# SCH_sensoresAgua_2026-07-03.net
KiCad netlist of a schematic drawn in EasyEDA
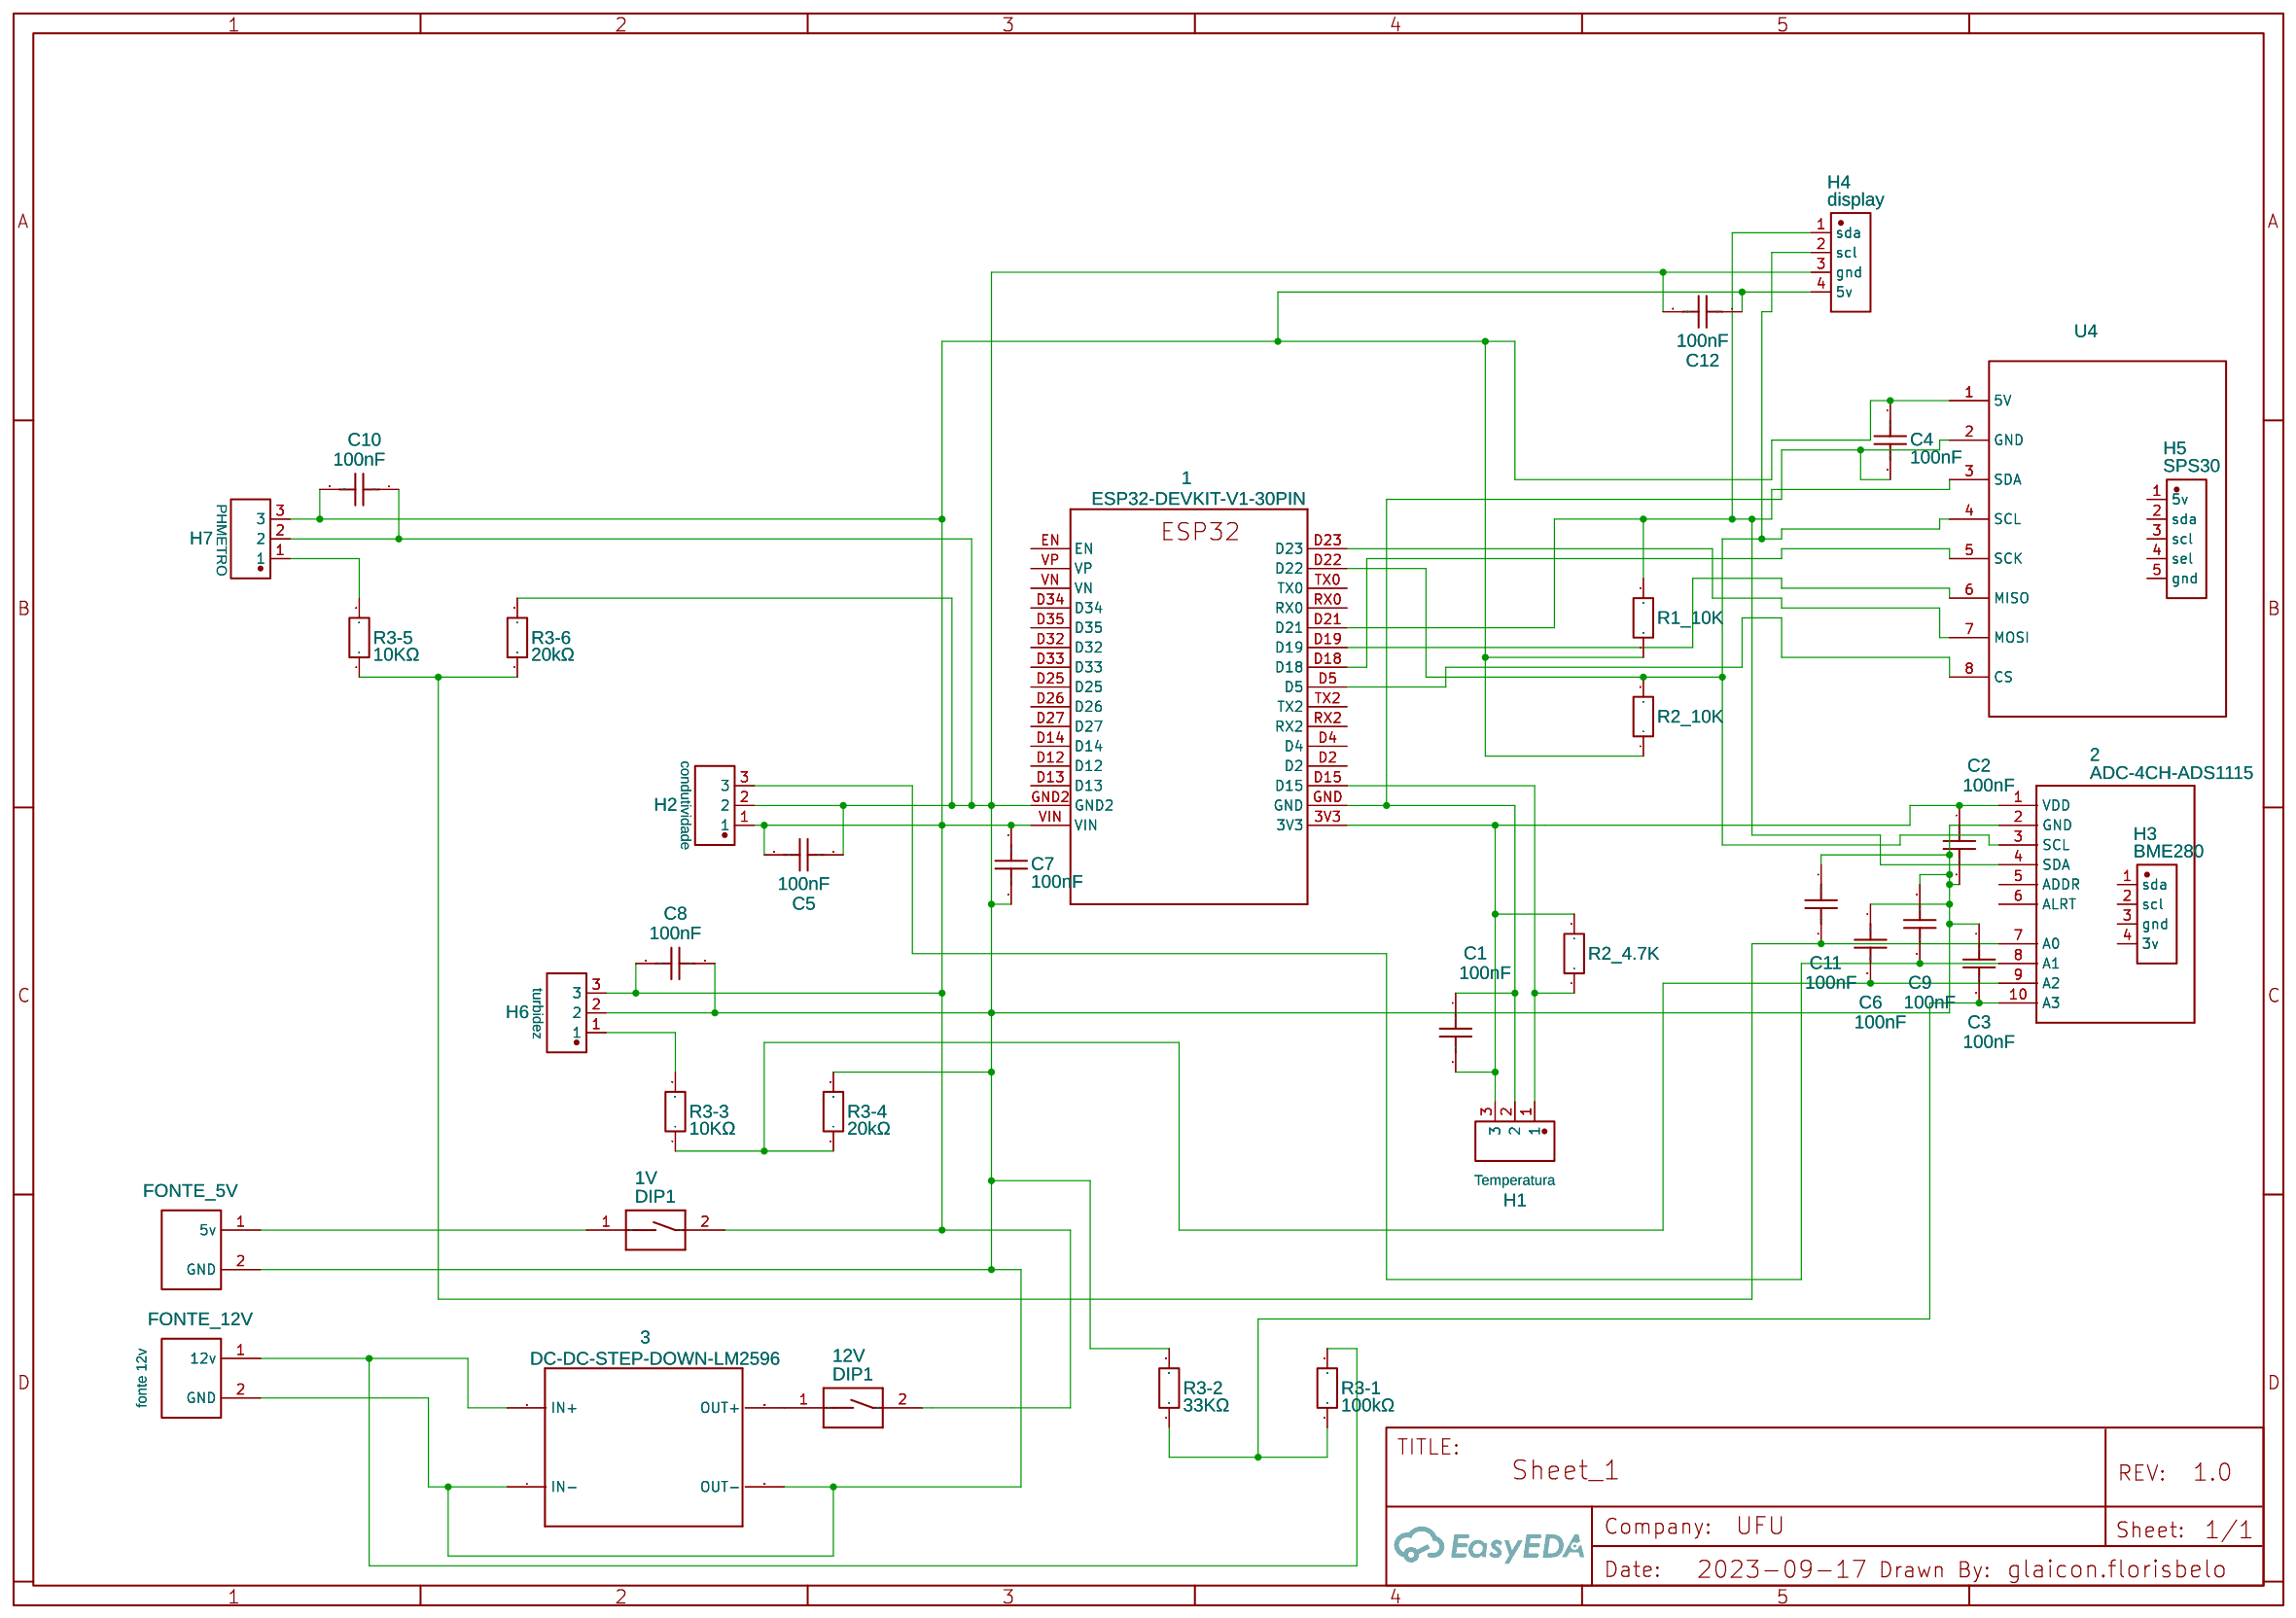
[diagram p0: schematic sheet]

(export (version "E")
  (design (tool "Eeschema 10.0.6"))
  (components
    (comp (ref "1") (value "ESP32-DEVKIT-V1-30PIN") (libsource (lib "") (part "ESP32-DEVKIT-V1-30PIN")))
    (comp (ref "1V")
      (value "DIP1")
      (fields
        (field (name "Manufacturer Part") "A6TN-1101")
        (field (name "Manufacturer") "Omron Electronics Inc-EMC Div")
      )
      (libsource (lib "") (part "DIP1"))
    )
    (comp (ref "2") (value "ADC-4CH-ADS1115") (libsource (lib "") (part "ADC-4CH-ADS1115")))
    (comp (ref "3") (value "DC-DC-STEP-DOWN-LM2596") (libsource (lib "") (part "DC-DC-STEP-DOWN-LM2596")))
    (comp (ref "12V")
      (value "DIP1")
      (fields
        (field (name "Manufacturer Part") "A6TN-1101")
        (field (name "Manufacturer") "Omron Electronics Inc-EMC Div")
      )
      (libsource (lib "") (part "DIP1_1"))
    )
    (comp (ref "C1")
      (value "100nF")
      (fields
        (field (name "Manufacturer Part") "CC1H104MC1FD3F6C10MF")
        (field (name "Manufacturer") "Dersonic(德尔创)")
      )
      (libsource (lib "") (part "CC1H104MC1FD3F6C10MF_1"))
    )
    (comp (ref "C2")
      (value "100nF")
      (fields
        (field (name "Manufacturer Part") "CC1H104MC1FD3F6C10MF")
        (field (name "Manufacturer") "Dersonic(德尔创)")
      )
      (libsource (lib "") (part "CC1H104MC1FD3F6C10MF_1"))
    )
    (comp (ref "C3")
      (value "100nF")
      (fields
        (field (name "Manufacturer Part") "CC1H104MC1FD3F6C10MF")
        (field (name "Manufacturer") "Dersonic(德尔创)")
      )
      (libsource (lib "") (part "CC1H104MC1FD3F6C10MF_1"))
    )
    (comp (ref "C4")
      (value "100nF")
      (fields
        (field (name "Manufacturer Part") "CC1H104MC1FD3F6C10MF")
        (field (name "Manufacturer") "Dersonic(德尔创)")
      )
      (libsource (lib "") (part "CC1H104MC1FD3F6C10MF_1"))
    )
    (comp (ref "C5")
      (value "100nF")
      (fields
        (field (name "Manufacturer Part") "CC1H104MC1FD3F6C10MF")
        (field (name "Manufacturer") "Dersonic(德尔创)")
      )
      (libsource (lib "") (part "CC1H104MC1FD3F6C10MF"))
    )
    (comp (ref "C6")
      (value "100nF")
      (fields
        (field (name "Manufacturer Part") "CC1H104MC1FD3F6C10MF")
        (field (name "Manufacturer") "Dersonic(德尔创)")
      )
      (libsource (lib "") (part "CC1H104MC1FD3F6C10MF_1"))
    )
    (comp (ref "C7")
      (value "100nF")
      (fields
        (field (name "Manufacturer Part") "CC1H104MC1FD3F6C10MF")
        (field (name "Manufacturer") "Dersonic(德尔创)")
      )
      (libsource (lib "") (part "CC1H104MC1FD3F6C10MF_1"))
    )
    (comp (ref "C8")
      (value "100nF")
      (fields
        (field (name "Manufacturer Part") "CC1H104MC1FD3F6C10MF")
        (field (name "Manufacturer") "Dersonic(德尔创)")
      )
      (libsource (lib "") (part "CC1H104MC1FD3F6C10MF"))
    )
    (comp (ref "C9")
      (value "100nF")
      (fields
        (field (name "Manufacturer Part") "CC1H104MC1FD3F6C10MF")
        (field (name "Manufacturer") "Dersonic(德尔创)")
      )
      (libsource (lib "") (part "CC1H104MC1FD3F6C10MF_1"))
    )
    (comp (ref "C10")
      (value "100nF")
      (fields
        (field (name "Manufacturer Part") "CC1H104MC1FD3F6C10MF")
        (field (name "Manufacturer") "Dersonic(德尔创)")
      )
      (libsource (lib "") (part "CC1H104MC1FD3F6C10MF"))
    )
    (comp (ref "C11")
      (value "100nF")
      (fields
        (field (name "Manufacturer Part") "CC1H104MC1FD3F6C10MF")
        (field (name "Manufacturer") "Dersonic(德尔创)")
      )
      (libsource (lib "") (part "CC1H104MC1FD3F6C10MF_1"))
    )
    (comp (ref "C12")
      (value "100nF")
      (fields
        (field (name "Manufacturer Part") "CC1H104MC1FD3F6C10MF")
        (field (name "Manufacturer") "Dersonic(德尔创)")
      )
      (libsource (lib "") (part "CC1H104MC1FD3F6C10MF"))
    )
    (comp (ref "FONTE_5V")
      (value "CONN-TH_2P-P5.00_WJ300V-5.00-2P WJ300V-5.0-2P")
      (fields
        (field (name "Manufacturer Part") "WJ300V-5.0-2P")
        (field (name "Manufacturer") "KANGNEX(康奈克斯电气)")
      )
      (libsource (lib "") (part "WJ300V-5.0-2P"))
    )
    (comp (ref "FONTE_12V")
      (value "fonte 12v")
      (fields
        (field (name "Manufacturer Part") "WJ300V-5.0-2P")
        (field (name "Manufacturer") "KANGNEX(康奈克斯电气)")
      )
      (libsource (lib "") (part "WJ300V-5.0-2P_1"))
    )
    (comp (ref "H1")
      (value "Temperatura")
      (fields
        (field (name "Manufacturer Part") "X4611WV-03I-C28D40")
        (field (name "Manufacturer") "XKB Connectivity(中国星坤)")
      )
      (libsource (lib "") (part "X4611WV-03I-C28D40_1"))
    )
    (comp (ref "H2")
      (value "condutividade")
      (fields
        (field (name "Manufacturer Part") "X4611WV-03I-C28D40")
        (field (name "Manufacturer") "XKB Connectivity(中国星坤)")
      )
      (libsource (lib "") (part "X4611WV-03I-C28D40"))
    )
    (comp (ref "H3")
      (value "BME280")
      (fields (field (name "Manufacturer Part") "MTF185-104SY1") (field (name "Manufacturer") "MINTRON(明硕)"))
      (libsource (lib "") (part "MTF185-104SY1"))
    )
    (comp (ref "H4")
      (value "display")
      (fields (field (name "Manufacturer Part") "MTF185-104SY1") (field (name "Manufacturer") "MINTRON(明硕)"))
      (libsource (lib "") (part "MTF185-104SY1_1"))
    )
    (comp (ref "H5")
      (value "SPS30")
      (fields (field (name "Manufacturer Part") "MTF185-105SY1") (field (name "Manufacturer") "MINTRON(明硕)"))
      (libsource (lib "") (part "MTF185-105SY1"))
    )
    (comp (ref "H6")
      (value "turbidez")
      (fields
        (field (name "Manufacturer Part") "X4611WV-03I-C28D40")
        (field (name "Manufacturer") "XKB Connectivity(中国星坤)")
      )
      (libsource (lib "") (part "X4611WV-03I-C28D40"))
    )
    (comp (ref "H7")
      (value "PHMETRO")
      (fields
        (field (name "Manufacturer Part") "X4611WV-03I-C28D40")
        (field (name "Manufacturer") "XKB Connectivity(中国星坤)")
      )
      (libsource (lib "") (part "X4611WV-03I-C28D40"))
    )
    (comp (ref "R1_10K")
      (value "100kΩ")
      (fields (field (name "Manufacturer Part") "CR1/4W-100K±5%-ST26") (field (name "Manufacturer") "VO(翔胜)"))
      (libsource (lib "") (part "CR1/4W-100K±5%-ST26"))
    )
    (comp (ref "R2_4.7K")
      (value "100kΩ")
      (fields (field (name "Manufacturer Part") "CR1/4W-100K±5%-ST26") (field (name "Manufacturer") "VO(翔胜)"))
      (libsource (lib "") (part "CR1/4W-100K±5%-ST26_2"))
    )
    (comp (ref "R2_10K")
      (value "100kΩ")
      (fields (field (name "Manufacturer Part") "CR1/4W-100K±5%-ST26") (field (name "Manufacturer") "VO(翔胜)"))
      (libsource (lib "") (part "CR1/4W-100K±5%-ST26_1"))
    )
    (comp (ref "R3-1")
      (value "100kΩ")
      (fields (field (name "Manufacturer Part") "CR1/4W-330Ω±5%-ST26") (field (name "Manufacturer") "VO(翔胜)"))
      (libsource (lib "") (part "CR1/4W-330Ω±5%-ST26"))
    )
    (comp (ref "R3-2")
      (value "33KΩ")
      (fields (field (name "Manufacturer Part") "CR1/4W-330Ω±5%-ST26") (field (name "Manufacturer") "VO(翔胜)"))
      (libsource (lib "") (part "CR1/4W-330Ω±5%-ST26"))
    )
    (comp (ref "R3-3")
      (value "10KΩ")
      (fields (field (name "Manufacturer Part") "CR1/4W-330Ω±5%-ST26") (field (name "Manufacturer") "VO(翔胜)"))
      (libsource (lib "") (part "CR1/4W-330Ω±5%-ST26"))
    )
    (comp (ref "R3-4")
      (value "20kΩ")
      (fields (field (name "Manufacturer Part") "CR1/4W-330Ω±5%-ST26") (field (name "Manufacturer") "VO(翔胜)"))
      (libsource (lib "") (part "CR1/4W-330Ω±5%-ST26"))
    )
    (comp (ref "R3-5")
      (value "10KΩ")
      (fields (field (name "Manufacturer Part") "CR1/4W-330Ω±5%-ST26") (field (name "Manufacturer") "VO(翔胜)"))
      (libsource (lib "") (part "CR1/4W-330Ω±5%-ST26"))
    )
    (comp (ref "R3-6")
      (value "20kΩ")
      (fields (field (name "Manufacturer Part") "CR1/4W-330Ω±5%-ST26") (field (name "Manufacturer") "VO(翔胜)"))
      (libsource (lib "") (part "CR1/4W-330Ω±5%-ST26"))
    )
    (comp (ref "U4") (value "NO") (libsource (lib "") (part "DATALOGGER-DFROBOT")))
  )
  (nets
    (net (code "1") (name "Net-(1-PadD15)") (class "Default")
      (node (ref "1") (pin "D15") (pinfunction "D15_D15") (pintype "unspecified"))
      (node (ref "H1") (pin "1") (pinfunction "1_1") (pintype "unspecified"))
      (node (ref "R2_4.7K") (pin "1") (pinfunction "1_1") (pintype "unspecified"))
    )
    (net (code "2") (name "Net-(2-A0)") (class "Default")
      (node (ref "2") (pin "7") (pinfunction "A0_7") (pintype "bidirectional"))
      (node (ref "C11") (pin "2") (pinfunction "2_2") (pintype "unspecified"))
      (node (ref "R3-5") (pin "1") (pinfunction "1_1") (pintype "unspecified"))
      (node (ref "R3-6") (pin "1") (pinfunction "1_1") (pintype "unspecified"))
    )
    (net (code "3") (name "Net-(2-A1)") (class "Default")
      (node (ref "2") (pin "8") (pinfunction "A1_8") (pintype "bidirectional"))
      (node (ref "C9") (pin "2") (pinfunction "2_2") (pintype "unspecified"))
      (node (ref "H2") (pin "3") (pinfunction "3_3") (pintype "unspecified"))
    )
    (net (code "4") (name "Net-(2-A2)") (class "Default")
      (node (ref "2") (pin "9") (pinfunction "A2_9") (pintype "bidirectional"))
      (node (ref "C6") (pin "2") (pinfunction "2_2") (pintype "unspecified"))
      (node (ref "R3-3") (pin "1") (pinfunction "1_1") (pintype "unspecified"))
      (node (ref "R3-4") (pin "1") (pinfunction "1_1") (pintype "unspecified"))
    )
    (net (code "5") (name "Net-(2-A3)") (class "Default")
      (node (ref "2") (pin "10") (pinfunction "A3_10") (pintype "bidirectional"))
      (node (ref "C3") (pin "2") (pinfunction "2_2") (pintype "unspecified"))
      (node (ref "R3-1") (pin "1") (pinfunction "1_1") (pintype "unspecified"))
      (node (ref "R3-2") (pin "1") (pinfunction "1_1") (pintype "unspecified"))
    )
    (net (code "6") (name "Net-(2-GND)") (class "Default")
      (node (ref "1") (pin "GND2") (pinfunction "GND2_GND2") (pintype "unspecified"))
      (node (ref "2") (pin "2") (pinfunction "GND_2") (pintype "bidirectional"))
      (node (ref "3") (pin "IN-") (pinfunction "IN-_IN-") (pintype "bidirectional"))
      (node (ref "3") (pin "OUT-") (pinfunction "OUT-_OUT-") (pintype "bidirectional"))
      (node (ref "C10") (pin "1") (pinfunction "1_1") (pintype "unspecified"))
      (node (ref "C11") (pin "1") (pinfunction "1_1") (pintype "unspecified"))
      (node (ref "C12") (pin "2") (pinfunction "2_2") (pintype "unspecified"))
      (node (ref "C2") (pin "2") (pinfunction "2_2") (pintype "unspecified"))
      (node (ref "C3") (pin "1") (pinfunction "1_1") (pintype "unspecified"))
      (node (ref "C5") (pin "1") (pinfunction "1_1") (pintype "unspecified"))
      (node (ref "C6") (pin "1") (pinfunction "1_1") (pintype "unspecified"))
      (node (ref "C7") (pin "2") (pinfunction "2_2") (pintype "unspecified"))
      (node (ref "C8") (pin "1") (pinfunction "1_1") (pintype "unspecified"))
      (node (ref "C9") (pin "1") (pinfunction "1_1") (pintype "unspecified"))
      (node (ref "FONTE_12V") (pin "2") (pinfunction "GND_2") (pintype "unspecified"))
      (node (ref "FONTE_5V") (pin "2") (pinfunction "GND_2") (pintype "unspecified"))
      (node (ref "H2") (pin "2") (pinfunction "2_2") (pintype "unspecified"))
      (node (ref "H4") (pin "3") (pinfunction "gnd_3") (pintype "unspecified"))
      (node (ref "H6") (pin "2") (pinfunction "2_2") (pintype "unspecified"))
      (node (ref "H7") (pin "2") (pinfunction "2_2") (pintype "unspecified"))
      (node (ref "R3-2") (pin "2") (pinfunction "2_2") (pintype "unspecified"))
      (node (ref "R3-4") (pin "2") (pinfunction "2_2") (pintype "unspecified"))
      (node (ref "R3-6") (pin "2") (pinfunction "2_2") (pintype "unspecified"))
    )
    (net (code "7") (name "Net-(2-SCL)") (class "Default")
      (node (ref "1") (pin "D22") (pinfunction "D22_D22") (pintype "unspecified"))
      (node (ref "2") (pin "3") (pinfunction "SCL_3") (pintype "bidirectional"))
      (node (ref "H4") (pin "2") (pinfunction "scl_2") (pintype "unspecified"))
      (node (ref "R2_10K") (pin "2") (pinfunction "2_2") (pintype "unspecified"))
      (node (ref "U4") (pin "4") (pinfunction "SCL_4") (pintype "unspecified"))
    )
    (net (code "8") (name "Net-(2-SDA)") (class "Default")
      (node (ref "1") (pin "D21") (pinfunction "D21_D21") (pintype "unspecified"))
      (node (ref "2") (pin "4") (pinfunction "SDA_4") (pintype "bidirectional"))
      (node (ref "H4") (pin "1") (pinfunction "sda_1") (pintype "unspecified"))
      (node (ref "R1_10K") (pin "1") (pinfunction "1_1") (pintype "unspecified"))
      (node (ref "U4") (pin "3") (pinfunction "SDA_3") (pintype "unspecified"))
    )
    (net (code "9") (name "Net-(2-VDD)") (class "Default")
      (node (ref "1") (pin "3V3") (pinfunction "3V3_3V3") (pintype "unspecified"))
      (node (ref "2") (pin "1") (pinfunction "VDD_1") (pintype "bidirectional"))
      (node (ref "C1") (pin "2") (pinfunction "2_2") (pintype "unspecified"))
      (node (ref "C2") (pin "1") (pinfunction "1_1") (pintype "unspecified"))
      (node (ref "H1") (pin "3") (pinfunction "3_3") (pintype "unspecified"))
      (node (ref "R2_4.7K") (pin "2") (pinfunction "2_2") (pintype "unspecified"))
    )
    (net (code "10") (name "Net-(12V-Pad1)") (class "Default")
      (node (ref "12V") (pin "1") (pinfunction "1_1") (pintype "unspecified"))
      (node (ref "3") (pin "OUT+") (pinfunction "OUT+_OUT+") (pintype "bidirectional"))
    )
    (net (code "11") (name "Net-(FONTE_5V-5v)") (class "Default")
      (node (ref "1V") (pin "1") (pinfunction "1_1") (pintype "unspecified"))
      (node (ref "FONTE_5V") (pin "1") (pinfunction "5v_1") (pintype "unspecified"))
    )
    (net (code "12") (name "Net-(FONTE_12V-12v)") (class "Default")
      (node (ref "3") (pin "IN+") (pinfunction "IN+_IN+") (pintype "bidirectional"))
      (node (ref "FONTE_12V") (pin "1") (pinfunction "12v_1") (pintype "unspecified"))
      (node (ref "R3-1") (pin "2") (pinfunction "2_2") (pintype "unspecified"))
    )
    (net (code "13") (name "Net-(H4-5v)") (class "Default")
      (node (ref "1") (pin "VIN") (pinfunction "VIN_VIN") (pintype "unspecified"))
      (node (ref "12V") (pin "2") (pinfunction "2_2") (pintype "unspecified"))
      (node (ref "1V") (pin "2") (pinfunction "2_2") (pintype "unspecified"))
      (node (ref "C10") (pin "2") (pinfunction "2_2") (pintype "unspecified"))
      (node (ref "C12") (pin "1") (pinfunction "1_1") (pintype "unspecified"))
      (node (ref "C4") (pin "1") (pinfunction "1_1") (pintype "unspecified"))
      (node (ref "C5") (pin "2") (pinfunction "2_2") (pintype "unspecified"))
      (node (ref "C7") (pin "1") (pinfunction "1_1") (pintype "unspecified"))
      (node (ref "C8") (pin "2") (pinfunction "2_2") (pintype "unspecified"))
      (node (ref "H2") (pin "1") (pinfunction "1_1") (pintype "unspecified"))
      (node (ref "H4") (pin "4") (pinfunction "5v_4") (pintype "unspecified"))
      (node (ref "H6") (pin "3") (pinfunction "3_3") (pintype "unspecified"))
      (node (ref "H7") (pin "3") (pinfunction "3_3") (pintype "unspecified"))
      (node (ref "R1_10K") (pin "2") (pinfunction "2_2") (pintype "unspecified"))
      (node (ref "R2_10K") (pin "1") (pinfunction "1_1") (pintype "unspecified"))
      (node (ref "U4") (pin "1") (pinfunction "5V_1") (pintype "unspecified"))
    )
    (net (code "14") (name "Net-(H6-Pad1)") (class "Default")
      (node (ref "H6") (pin "1") (pinfunction "1_1") (pintype "unspecified"))
      (node (ref "R3-3") (pin "2") (pinfunction "2_2") (pintype "unspecified"))
    )
    (net (code "15") (name "Net-(H7-Pad1)") (class "Default")
      (node (ref "H7") (pin "1") (pinfunction "1_1") (pintype "unspecified"))
      (node (ref "R3-5") (pin "2") (pinfunction "2_2") (pintype "unspecified"))
    )
    (net (code "16") (name "Net-(U4-CS)") (class "Default")
      (node (ref "1") (pin "D5") (pinfunction "D5_D5") (pintype "unspecified"))
      (node (ref "U4") (pin "8") (pinfunction "CS_8") (pintype "unspecified"))
    )
    (net (code "17") (name "Net-(U4-GND)") (class "Default")
      (node (ref "1") (pin "GND") (pinfunction "GND_GND") (pintype "unspecified"))
      (node (ref "C1") (pin "1") (pinfunction "1_1") (pintype "unspecified"))
      (node (ref "C4") (pin "2") (pinfunction "2_2") (pintype "unspecified"))
      (node (ref "H1") (pin "2") (pinfunction "2_2") (pintype "unspecified"))
      (node (ref "U4") (pin "2") (pinfunction "GND_2") (pintype "unspecified"))
    )
    (net (code "18") (name "Net-(U4-MISO)") (class "Default")
      (node (ref "1") (pin "D19") (pinfunction "D19_D19") (pintype "unspecified"))
      (node (ref "U4") (pin "6") (pinfunction "MISO_6") (pintype "unspecified"))
    )
    (net (code "19") (name "Net-(U4-MOSI)") (class "Default")
      (node (ref "1") (pin "D23") (pinfunction "D23_D23") (pintype "unspecified"))
      (node (ref "U4") (pin "7") (pinfunction "MOSI_7") (pintype "unspecified"))
    )
    (net (code "20") (name "Net-(U4-SCK)") (class "Default")
      (node (ref "1") (pin "D18") (pinfunction "D18_D18") (pintype "unspecified"))
      (node (ref "U4") (pin "5") (pinfunction "SCK_5") (pintype "unspecified"))
    )
    (net (code "21") (name "unconnected-(1-PadD2)") (class "Default")
      (node (ref "1") (pin "D2") (pinfunction "D2_D2") (pintype "unspecified"))
    )
    (net (code "22") (name "unconnected-(1-PadD4)") (class "Default")
      (node (ref "1") (pin "D4") (pinfunction "D4_D4") (pintype "unspecified"))
    )
    (net (code "23") (name "unconnected-(1-PadD12)") (class "Default")
      (node (ref "1") (pin "D12") (pinfunction "D12_D12") (pintype "unspecified"))
    )
    (net (code "24") (name "unconnected-(1-PadD13)") (class "Default")
      (node (ref "1") (pin "D13") (pinfunction "D13_D13") (pintype "unspecified"))
    )
    (net (code "25") (name "unconnected-(1-PadD14)") (class "Default")
      (node (ref "1") (pin "D14") (pinfunction "D14_D14") (pintype "unspecified"))
    )
    (net (code "26") (name "unconnected-(1-PadD25)") (class "Default")
      (node (ref "1") (pin "D25") (pinfunction "D25_D25") (pintype "unspecified"))
    )
    (net (code "27") (name "unconnected-(1-PadD26)") (class "Default")
      (node (ref "1") (pin "D26") (pinfunction "D26_D26") (pintype "unspecified"))
    )
    (net (code "28") (name "unconnected-(1-PadD27)") (class "Default")
      (node (ref "1") (pin "D27") (pinfunction "D27_D27") (pintype "unspecified"))
    )
    (net (code "29") (name "unconnected-(1-PadD32)") (class "Default")
      (node (ref "1") (pin "D32") (pinfunction "D32_D32") (pintype "unspecified"))
    )
    (net (code "30") (name "unconnected-(1-PadD33)") (class "Default")
      (node (ref "1") (pin "D33") (pinfunction "D33_D33") (pintype "unspecified"))
    )
    (net (code "31") (name "unconnected-(1-PadD34)") (class "Default")
      (node (ref "1") (pin "D34") (pinfunction "D34_D34") (pintype "unspecified"))
    )
    (net (code "32") (name "unconnected-(1-PadD35)") (class "Default")
      (node (ref "1") (pin "D35") (pinfunction "D35_D35") (pintype "unspecified"))
    )
    (net (code "33") (name "unconnected-(1-PadEN)") (class "Default")
      (node (ref "1") (pin "EN") (pinfunction "EN_EN") (pintype "unspecified"))
    )
    (net (code "34") (name "unconnected-(1-PadRX0)") (class "Default")
      (node (ref "1") (pin "RX0") (pinfunction "RX0_RX0") (pintype "unspecified"))
    )
    (net (code "35") (name "unconnected-(1-PadRX2)") (class "Default")
      (node (ref "1") (pin "RX2") (pinfunction "RX2_RX2") (pintype "unspecified"))
    )
    (net (code "36") (name "unconnected-(1-PadTX0)") (class "Default")
      (node (ref "1") (pin "TX0") (pinfunction "TX0_TX0") (pintype "unspecified"))
    )
    (net (code "37") (name "unconnected-(1-PadTX2)") (class "Default")
      (node (ref "1") (pin "TX2") (pinfunction "TX2_TX2") (pintype "unspecified"))
    )
    (net (code "38") (name "unconnected-(1-PadVN)") (class "Default")
      (node (ref "1") (pin "VN") (pinfunction "VN_VN") (pintype "unspecified"))
    )
    (net (code "39") (name "unconnected-(1-PadVP)") (class "Default")
      (node (ref "1") (pin "VP") (pinfunction "VP_VP") (pintype "unspecified"))
    )
    (net (code "40") (name "unconnected-(2-ADDR-Pad5)") (class "Default")
      (node (ref "2") (pin "5") (pinfunction "ADDR_5") (pintype "bidirectional"))
    )
    (net (code "41") (name "unconnected-(2-ALRT-Pad6)") (class "Default")
      (node (ref "2") (pin "6") (pinfunction "ALRT_6") (pintype "bidirectional"))
    )
    (net (code "42") (name "unconnected-(H3-3v-Pad4)") (class "Default")
      (node (ref "H3") (pin "4") (pinfunction "3v_4") (pintype "unspecified"))
    )
    (net (code "43") (name "unconnected-(H3-gnd-Pad3)") (class "Default")
      (node (ref "H3") (pin "3") (pinfunction "gnd_3") (pintype "unspecified"))
    )
    (net (code "44") (name "unconnected-(H3-scl-Pad2)") (class "Default")
      (node (ref "H3") (pin "2") (pinfunction "scl_2") (pintype "unspecified"))
    )
    (net (code "45") (name "unconnected-(H3-sda-Pad1)") (class "Default")
      (node (ref "H3") (pin "1") (pinfunction "sda_1") (pintype "unspecified"))
    )
    (net (code "46") (name "unconnected-(H5-5v-Pad1)") (class "Default")
      (node (ref "H5") (pin "1") (pinfunction "5v_1") (pintype "unspecified"))
    )
    (net (code "47") (name "unconnected-(H5-gnd-Pad5)") (class "Default")
      (node (ref "H5") (pin "5") (pinfunction "gnd_5") (pintype "unspecified"))
    )
    (net (code "48") (name "unconnected-(H5-scl-Pad3)") (class "Default")
      (node (ref "H5") (pin "3") (pinfunction "scl_3") (pintype "unspecified"))
    )
    (net (code "49") (name "unconnected-(H5-sda-Pad2)") (class "Default")
      (node (ref "H5") (pin "2") (pinfunction "sda_2") (pintype "unspecified"))
    )
    (net (code "50") (name "unconnected-(H5-sel-Pad4)") (class "Default")
      (node (ref "H5") (pin "4") (pinfunction "sel_4") (pintype "unspecified"))
    )
  )
)
